# transmitter.net
KiCad netlist of a schematic drawn in EAGLE
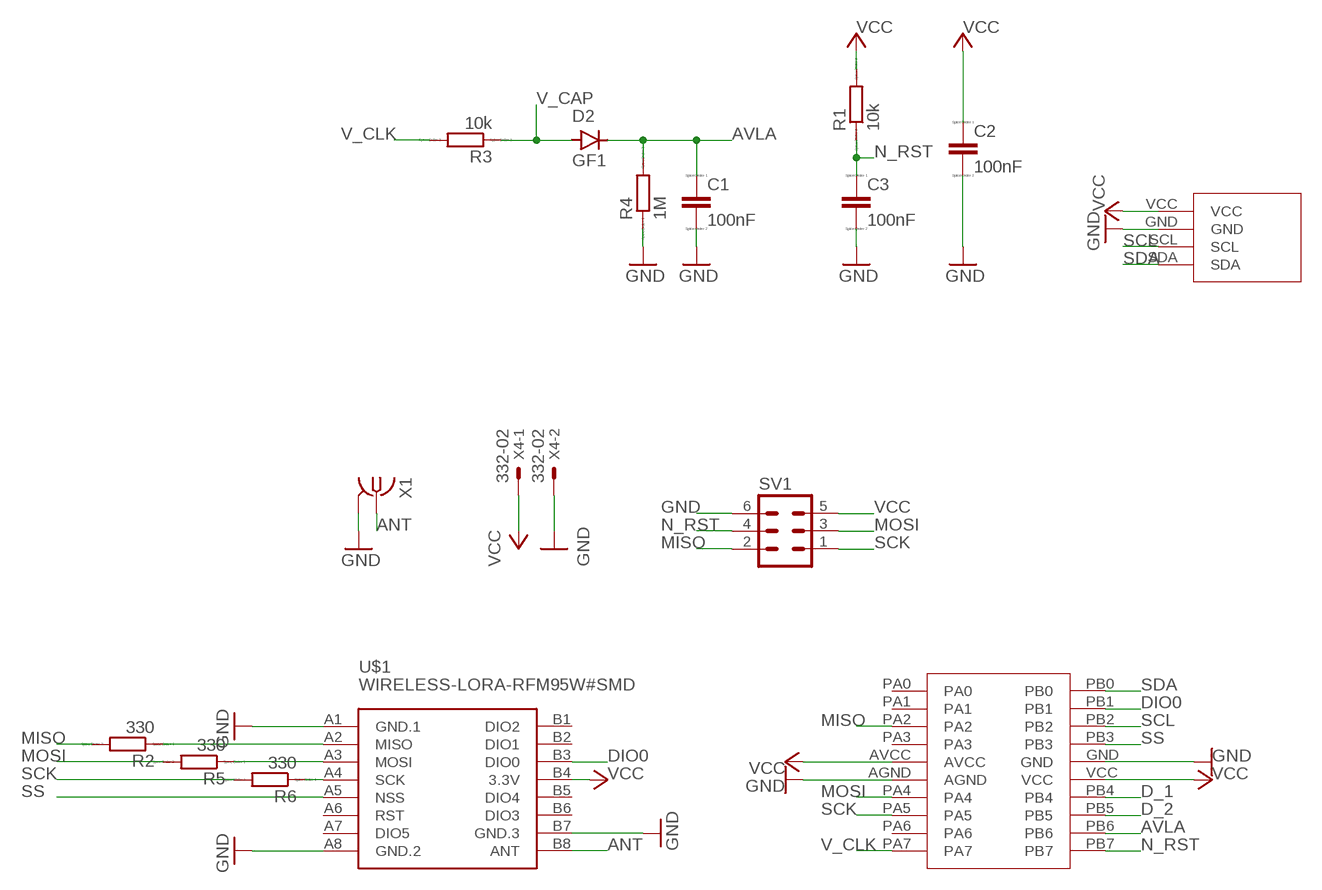
[diagram p0: schematic, sheet 1]

(export (version "E")
  (design (tool "Eeschema 10.0.6"))
  (components
    (comp (ref "ATTINY87_1")
      (value "ATTINY87_SOIC")
      (footprint "eagle-import:20-SOIC")
      (libsource (lib "eagle-import") (part "ATTINY87_SOIC"))
    )
    (comp (ref "C1")
      (value "100nF")
      (footprint "eagle-import:C1206")
      (libsource (lib "eagle-import") (part "CC1206"))
    )
    (comp (ref "C2")
      (value "100nF")
      (footprint "eagle-import:C1206")
      (libsource (lib "eagle-import") (part "CC1206"))
    )
    (comp (ref "C3")
      (value "100nF")
      (footprint "eagle-import:C1206")
      (libsource (lib "eagle-import") (part "CC1206"))
    )
    (comp (ref "D2")
      (value "GF1")
      (footprint "eagle-import:SMA-DO214AC")
      (libsource (lib "eagle-import") (part "GF1"))
    )
    (comp (ref "GY-68-1")
      (value "GY-68-4")
      (footprint "eagle-import:GY-68-4")
      (libsource (lib "eagle-import") (part "GY-68-4"))
    )
    (comp (ref "R1")
      (value "10k")
      (footprint "eagle-import:R0805")
      (libsource (lib "eagle-import") (part "R"))
    )
    (comp (ref "R2")
      (value "330")
      (footprint "eagle-import:R0805")
      (libsource (lib "eagle-import") (part "R"))
    )
    (comp (ref "R3")
      (value "10k")
      (footprint "eagle-import:R0805")
      (libsource (lib "eagle-import") (part "R"))
    )
    (comp (ref "R4")
      (value "1M")
      (footprint "eagle-import:R0805")
      (libsource (lib "eagle-import") (part "R"))
    )
    (comp (ref "R5")
      (value "330")
      (footprint "eagle-import:R0805")
      (libsource (lib "eagle-import") (part "R"))
    )
    (comp (ref "R6")
      (value "330")
      (footprint "eagle-import:R0805")
      (libsource (lib "eagle-import") (part "R"))
    )
    (comp (ref "SV1")
      (value "MA03-2")
      (footprint "eagle-import:MA03-2")
      (libsource (lib "eagle-import") (part "MA03-2"))
    )
    (comp (ref "U$1")
      (value "WIRELESS-LORA-RFM95W#SMD")
      (footprint "eagle-import:WIRELESS-LORA-RFM95W#SMD")
      (libsource (lib "eagle-import") (part "WIRELESS-LORA-RFM95W#SMD"))
    )
    (comp (ref "X1")
      (value "BU-SMA-G")
      (footprint "eagle-import:BU-SMA-G")
      (libsource (lib "eagle-import") (part "BU-SMA-G"))
    )
    (comp (ref "X4")
      (value "332-02")
      (footprint "eagle-import:332-02")
      (libsource (lib "eagle-import") (part "332-02"))
    )
  )
  (nets
    (net (code "1") (name "/ANT") (class "Default")
      (node (ref "U$1") (pin "B8") (pinfunction "ANT_B8") (pintype "passive"))
      (node (ref "X1") (pin "1") (pinfunction "1_1") (pintype "passive"))
    )
    (net (code "2") (name "/AVLA") (class "Default")
      (node (ref "ATTINY87_1") (pin "PB6") (pinfunction "PB6_PB6") (pintype "bidirectional"))
      (node (ref "C1") (pin "1") (pinfunction "1_1") (pintype "passive"))
      (node (ref "D2") (pin "K") (pinfunction "C_K") (pintype "passive"))
      (node (ref "R4") (pin "2") (pinfunction "2_2") (pintype "passive"))
    )
    (net (code "3") (name "/DIO0") (class "Default")
      (node (ref "ATTINY87_1") (pin "PB1") (pinfunction "PB1_PB1") (pintype "bidirectional"))
      (node (ref "U$1") (pin "B3") (pinfunction "DIO0_B3") (pintype "bidirectional"))
    )
    (net (code "4") (name "/D_1") (class "Default")
      (node (ref "ATTINY87_1") (pin "PB4") (pinfunction "PB4_PB4") (pintype "bidirectional"))
    )
    (net (code "5") (name "/D_2") (class "Default")
      (node (ref "ATTINY87_1") (pin "PB5") (pinfunction "PB5_PB5") (pintype "bidirectional"))
    )
    (net (code "6") (name "/MISO") (class "Default")
      (node (ref "ATTINY87_1") (pin "PA2") (pinfunction "PA2_PA2") (pintype "bidirectional"))
      (node (ref "R2") (pin "2") (pinfunction "2_2") (pintype "passive"))
      (node (ref "SV1") (pin "2") (pinfunction "2_2") (pintype "passive"))
    )
    (net (code "7") (name "/MOSI") (class "Default")
      (node (ref "ATTINY87_1") (pin "PA4") (pinfunction "PA4_PA4") (pintype "bidirectional"))
      (node (ref "R5") (pin "2") (pinfunction "2_2") (pintype "passive"))
      (node (ref "SV1") (pin "3") (pinfunction "3_3") (pintype "passive"))
    )
    (net (code "8") (name "/N_RST") (class "Default")
      (node (ref "ATTINY87_1") (pin "PB7") (pinfunction "PB7_PB7") (pintype "bidirectional"))
      (node (ref "C3") (pin "1") (pinfunction "1_1") (pintype "passive"))
      (node (ref "R1") (pin "1") (pinfunction "1_1") (pintype "passive"))
      (node (ref "SV1") (pin "4") (pinfunction "4_4") (pintype "passive"))
    )
    (net (code "9") (name "/SCK") (class "Default")
      (node (ref "ATTINY87_1") (pin "PA5") (pinfunction "PA5_PA5") (pintype "bidirectional"))
      (node (ref "R6") (pin "2") (pinfunction "2_2") (pintype "passive"))
      (node (ref "SV1") (pin "1") (pinfunction "1_1") (pintype "passive"))
    )
    (net (code "10") (name "/SCL") (class "Default")
      (node (ref "ATTINY87_1") (pin "PB2") (pinfunction "PB2_PB2") (pintype "bidirectional"))
      (node (ref "GY-68-1") (pin "SCL") (pinfunction "SCL_SCL") (pintype "bidirectional"))
    )
    (net (code "11") (name "/SDA") (class "Default")
      (node (ref "ATTINY87_1") (pin "PB0") (pinfunction "PB0_PB0") (pintype "bidirectional"))
      (node (ref "GY-68-1") (pin "SDA") (pinfunction "SDA_SDA") (pintype "bidirectional"))
    )
    (net (code "12") (name "/SS") (class "Default")
      (node (ref "ATTINY87_1") (pin "PB3") (pinfunction "PB3_PB3") (pintype "bidirectional"))
      (node (ref "U$1") (pin "A5") (pinfunction "NSS_A5") (pintype "bidirectional"))
    )
    (net (code "13") (name "/V_CAP") (class "Default")
      (node (ref "D2") (pin "A") (pinfunction "A_A") (pintype "passive"))
      (node (ref "R3") (pin "1") (pinfunction "1_1") (pintype "passive"))
    )
    (net (code "14") (name "/V_CLK") (class "Default")
      (node (ref "ATTINY87_1") (pin "PA7") (pinfunction "PA7_PA7") (pintype "bidirectional"))
      (node (ref "R3") (pin "2") (pinfunction "2_2") (pintype "passive"))
    )
    (net (code "15") (name "GND") (class "Default")
      (node (ref "ATTINY87_1") (pin "AGND") (pinfunction "AGND_AGND") (pintype "bidirectional"))
      (node (ref "ATTINY87_1") (pin "GND") (pinfunction "GND_GND") (pintype "bidirectional"))
      (node (ref "C1") (pin "2") (pinfunction "2_2") (pintype "passive"))
      (node (ref "C2") (pin "2") (pinfunction "2_2") (pintype "passive"))
      (node (ref "C3") (pin "2") (pinfunction "2_2") (pintype "passive"))
      (node (ref "GY-68-1") (pin "GND") (pinfunction "GND_GND") (pintype "bidirectional"))
      (node (ref "R4") (pin "1") (pinfunction "1_1") (pintype "passive"))
      (node (ref "SV1") (pin "6") (pinfunction "6_6") (pintype "passive"))
      (node (ref "U$1") (pin "A1") (pinfunction "GND.1_A1") (pintype "power_in"))
      (node (ref "U$1") (pin "A8") (pinfunction "GND.2_A8") (pintype "power_in"))
      (node (ref "U$1") (pin "B7") (pinfunction "GND.3_B7") (pintype "power_in"))
      (node (ref "X1") (pin "2") (pinfunction "2_2") (pintype "passive"))
      (node (ref "X1") (pin "3") (pinfunction "2_3") (pintype "passive"))
      (node (ref "X1") (pin "4") (pinfunction "2_4") (pintype "passive"))
      (node (ref "X1") (pin "5") (pinfunction "2_5") (pintype "passive"))
      (node (ref "X4") (pin "2") (pinfunction "S_2") (pintype "passive"))
    )
    (net (code "16") (name "Net-(U$1-MISO)") (class "Default")
      (node (ref "R2") (pin "1") (pinfunction "1_1") (pintype "passive"))
      (node (ref "U$1") (pin "A2") (pinfunction "MISO_A2") (pintype "bidirectional"))
    )
    (net (code "17") (name "Net-(U$1-MOSI)") (class "Default")
      (node (ref "R5") (pin "1") (pinfunction "1_1") (pintype "passive"))
      (node (ref "U$1") (pin "A3") (pinfunction "MOSI_A3") (pintype "bidirectional"))
    )
    (net (code "18") (name "Net-(U$1-SCK)") (class "Default")
      (node (ref "R6") (pin "1") (pinfunction "1_1") (pintype "passive"))
      (node (ref "U$1") (pin "A4") (pinfunction "SCK_A4") (pintype "bidirectional"))
    )
    (net (code "19") (name "VCC") (class "Default")
      (node (ref "ATTINY87_1") (pin "AVCC") (pinfunction "AVCC_AVCC") (pintype "bidirectional"))
      (node (ref "ATTINY87_1") (pin "VCC") (pinfunction "VCC_VCC") (pintype "bidirectional"))
      (node (ref "C2") (pin "1") (pinfunction "1_1") (pintype "passive"))
      (node (ref "GY-68-1") (pin "VCC") (pinfunction "VCC_VCC") (pintype "bidirectional"))
      (node (ref "R1") (pin "2") (pinfunction "2_2") (pintype "passive"))
      (node (ref "SV1") (pin "5") (pinfunction "5_5") (pintype "passive"))
      (node (ref "U$1") (pin "B4") (pinfunction "3.3V_B4") (pintype "power_in"))
      (node (ref "X4") (pin "1") (pinfunction "S_1") (pintype "passive"))
    )
    (net (code "20") (name "unconnected-(ATTINY87_1-PadPA0)") (class "Default")
      (node (ref "ATTINY87_1") (pin "PA0") (pinfunction "PA0_PA0") (pintype "bidirectional"))
    )
    (net (code "21") (name "unconnected-(ATTINY87_1-PadPA1)") (class "Default")
      (node (ref "ATTINY87_1") (pin "PA1") (pinfunction "PA1_PA1") (pintype "bidirectional"))
    )
    (net (code "22") (name "unconnected-(ATTINY87_1-PadPA3)") (class "Default")
      (node (ref "ATTINY87_1") (pin "PA3") (pinfunction "PA3_PA3") (pintype "bidirectional"))
    )
    (net (code "23") (name "unconnected-(ATTINY87_1-PadPA6)") (class "Default")
      (node (ref "ATTINY87_1") (pin "PA6") (pinfunction "PA6_PA6") (pintype "bidirectional"))
    )
    (net (code "24") (name "unconnected-(U$1-DIO1-PadB2)") (class "Default")
      (node (ref "U$1") (pin "B2") (pinfunction "DIO1_B2") (pintype "bidirectional"))
    )
    (net (code "25") (name "unconnected-(U$1-DIO2-PadB1)") (class "Default")
      (node (ref "U$1") (pin "B1") (pinfunction "DIO2_B1") (pintype "bidirectional"))
    )
    (net (code "26") (name "unconnected-(U$1-DIO3-PadB6)") (class "Default")
      (node (ref "U$1") (pin "B6") (pinfunction "DIO3_B6") (pintype "bidirectional"))
    )
    (net (code "27") (name "unconnected-(U$1-DIO4-PadB5)") (class "Default")
      (node (ref "U$1") (pin "B5") (pinfunction "DIO4_B5") (pintype "bidirectional"))
    )
    (net (code "28") (name "unconnected-(U$1-DIO5-PadA7)") (class "Default")
      (node (ref "U$1") (pin "A7") (pinfunction "DIO5_A7") (pintype "bidirectional"))
    )
    (net (code "29") (name "unconnected-(U$1-RST-PadA6)") (class "Default")
      (node (ref "U$1") (pin "A6") (pinfunction "RST_A6") (pintype "bidirectional"))
    )
  )
)
